# NG2092_TopLevel.net
KiCad netlist of a schematic drawn in Altium Designer
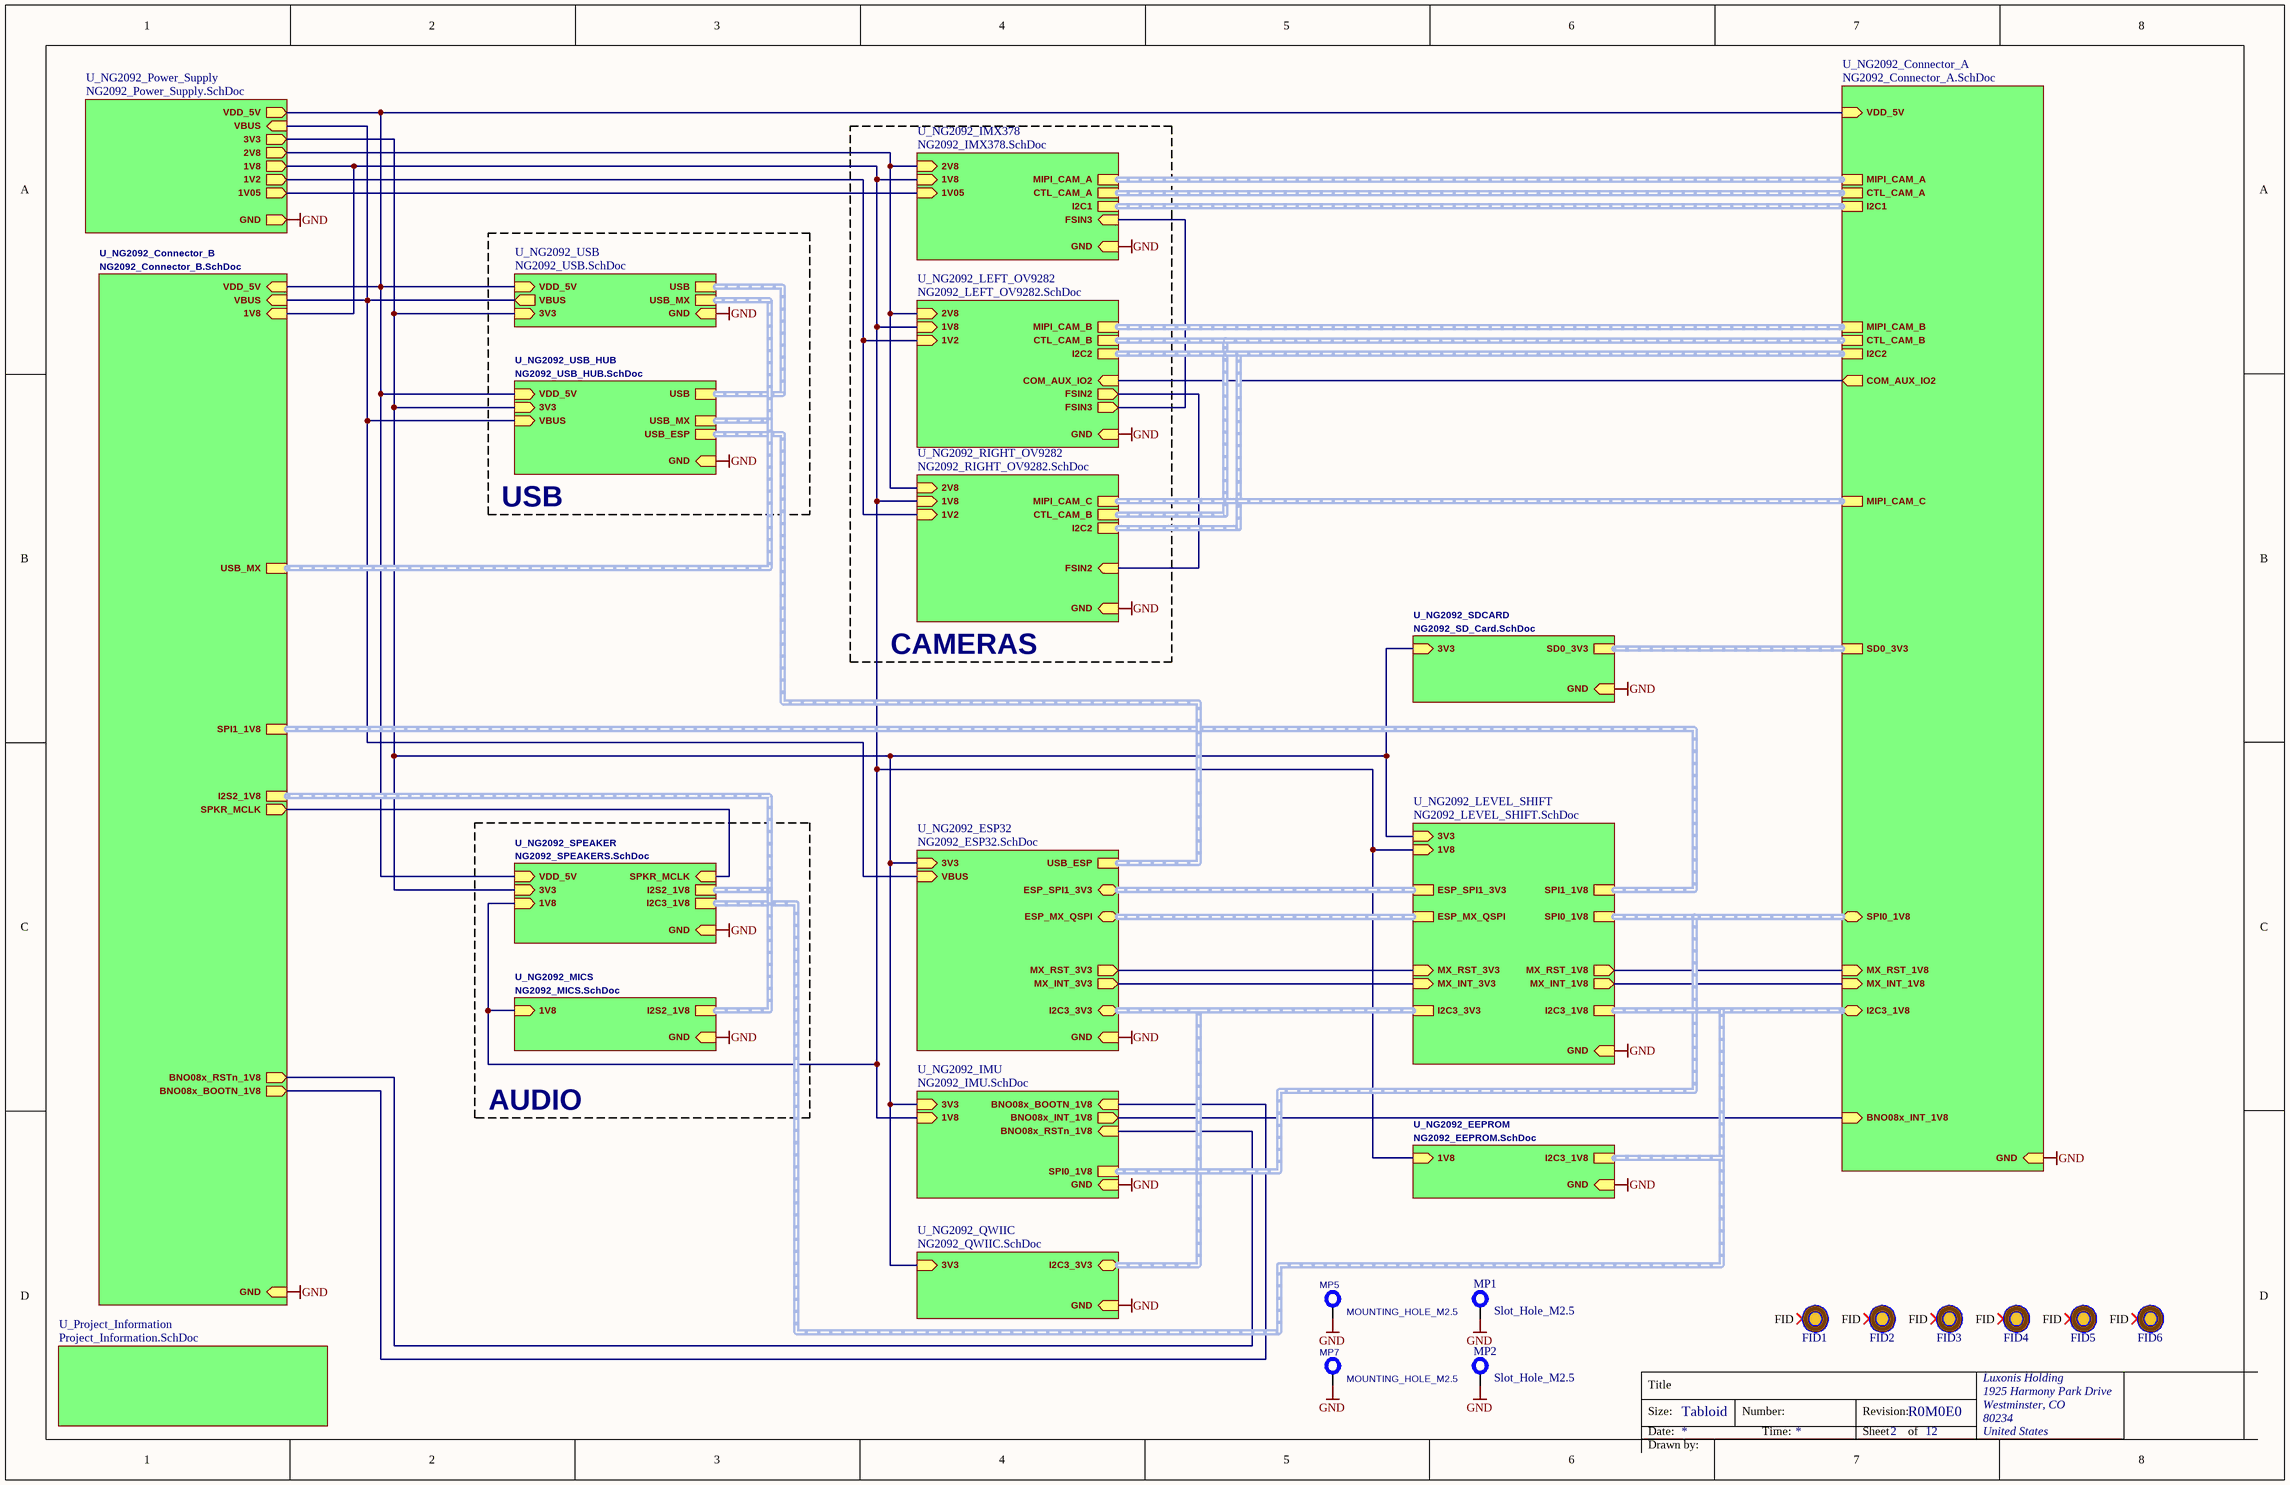
[diagram p0: NG2092_TopLevel.SchDoc]

(export (version "E")
  (design (tool "Eeschema 10.0.6"))
  (components
    (comp (ref "FID1")
      (value "FIDUCIAL_ROUND_1MM")
      (footprint "LuxonisMaster:FIDUCIAL_ROUND_1MM")
      (description "Fiducial with various available footprints")
      (libsource (lib "LuxonisMaster") (part "FIDUCIAL"))
    )
    (comp (ref "FID2")
      (value "FIDUCIAL_ROUND_1MM")
      (footprint "LuxonisMaster:FIDUCIAL_ROUND_1MM")
      (description "Fiducial with various available footprints")
      (libsource (lib "LuxonisMaster") (part "FIDUCIAL"))
    )
    (comp (ref "FID3")
      (value "FIDUCIAL_ROUND_1MM")
      (footprint "LuxonisMaster:FIDUCIAL_ROUND_1MM")
      (description "Fiducial with various available footprints")
      (libsource (lib "LuxonisMaster") (part "FIDUCIAL"))
    )
    (comp (ref "FID4")
      (value "FIDUCIAL_ROUND_1MM")
      (footprint "LuxonisMaster:FIDUCIAL_ROUND_1MM")
      (description "Fiducial with various available footprints")
      (libsource (lib "LuxonisMaster") (part "FIDUCIAL"))
    )
    (comp (ref "FID5")
      (value "FIDUCIAL_ROUND_1MM")
      (footprint "LuxonisMaster:FIDUCIAL_ROUND_1MM")
      (description "Fiducial with various available footprints")
      (libsource (lib "LuxonisMaster") (part "FIDUCIAL"))
    )
    (comp (ref "FID6")
      (value "FIDUCIAL_ROUND_1MM")
      (footprint "LuxonisMaster:FIDUCIAL_ROUND_1MM")
      (description "Fiducial with various available footprints")
      (libsource (lib "LuxonisMaster") (part "FIDUCIAL"))
    )
    (comp (ref "MP1")
      (value "Slot_Hole_M2.5")
      (footprint "Slot_Hole_M2.5")
      (description "=CurrentFootprint")
      (libsource (lib "NG2092") (part "MP_Slot-Holes"))
    )
    (comp (ref "MP2")
      (value "Slot_Hole_M2.5")
      (footprint "Slot_Hole_M2.5")
      (description "=CurrentFootprint")
      (libsource (lib "NG2092") (part "MP_Slot-Holes"))
    )
    (comp (ref "MP5")
      (value "MOUNTING_HOLE_M2.5")
      (footprint "LuxonisMaster:MOUNTING_HOLE_M2.5")
      (description "=CurrentFootprint")
      (libsource (lib "LuxonisMaster") (part "MP_Mounting-Holes"))
    )
    (comp (ref "MP7")
      (value "MOUNTING_HOLE_M2.5")
      (footprint "LuxonisMaster:MOUNTING_HOLE_M2.5")
      (description "=CurrentFootprint")
      (libsource (lib "LuxonisMaster") (part "MP_Mounting-Holes"))
    )
  )
  (nets
    (net (code "37") (name "GND") (class "Default")
      (node (ref "MP1") (pin "1") (pintype "passive"))
      (node (ref "MP2") (pin "1") (pintype "passive"))
      (node (ref "MP5") (pin "1") (pintype "passive"))
      (node (ref "MP7") (pin "1") (pintype "passive"))
    )
    (net (code "38") (name "unconnected-(FID1-PadFID)") (class "Default")
      (node (ref "FID1") (pin "FID") (pinfunction "FID_FID") (pintype "input+no_connect"))
    )
    (net (code "39") (name "unconnected-(FID2-PadFID)") (class "Default")
      (node (ref "FID2") (pin "FID") (pinfunction "FID_FID") (pintype "input+no_connect"))
    )
    (net (code "40") (name "unconnected-(FID3-PadFID)") (class "Default")
      (node (ref "FID3") (pin "FID") (pinfunction "FID_FID") (pintype "input+no_connect"))
    )
    (net (code "41") (name "unconnected-(FID4-PadFID)") (class "Default")
      (node (ref "FID4") (pin "FID") (pinfunction "FID_FID") (pintype "input+no_connect"))
    )
    (net (code "42") (name "unconnected-(FID5-PadFID)") (class "Default")
      (node (ref "FID5") (pin "FID") (pinfunction "FID_FID") (pintype "input+no_connect"))
    )
    (net (code "43") (name "unconnected-(FID6-PadFID)") (class "Default")
      (node (ref "FID6") (pin "FID") (pinfunction "FID_FID") (pintype "input+no_connect"))
    )
  )
)
